# powresupply.net
KiCad netlist of a schematic drawn in EAGLE
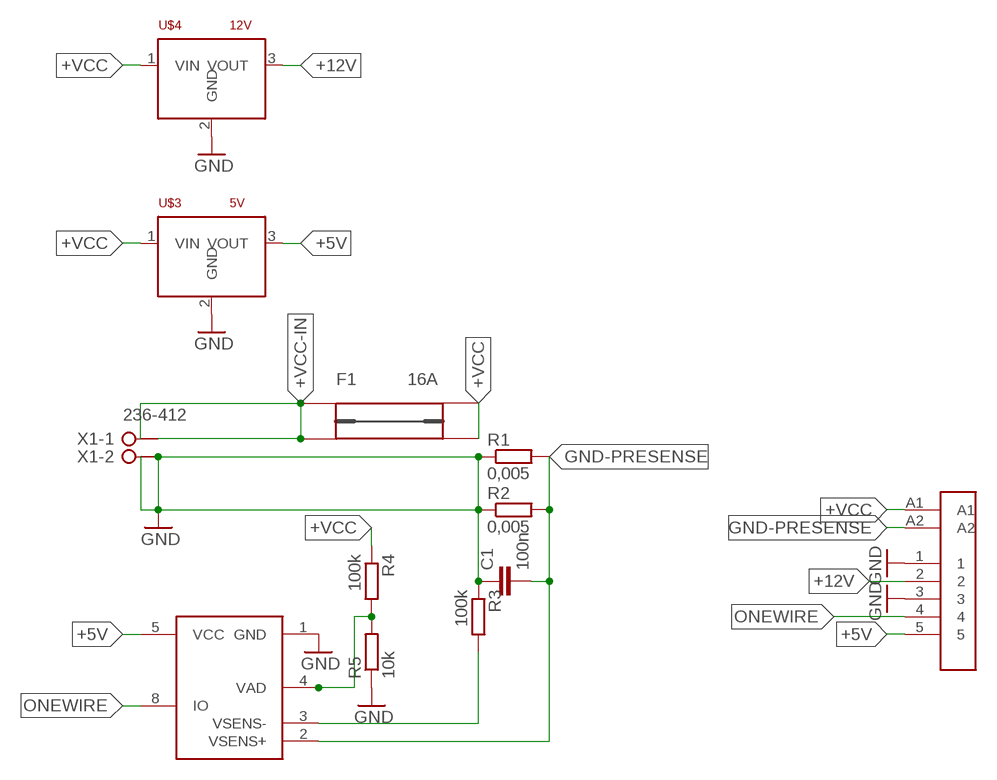
[diagram p0: schematic, sheet 1]

(export (version "E")
  (design (tool "Eeschema 10.0.6"))
  (components
    (comp (ref "C1")
      (value "100n")
      (footprint "eagle-import:C0805")
      (libsource (lib "eagle-import") (part "C-EUC0805"))
    )
    (comp (ref "F1")
      (value "16A")
      (footprint "eagle-import:1A3400")
      (libsource (lib "eagle-import") (part "BUSSMANN10X38"))
    )
    (comp (ref "R1")
      (value "0,005")
      (footprint "eagle-import:R2512")
      (libsource (lib "eagle-import") (part "R-EU_R2512"))
    )
    (comp (ref "R2")
      (value "0,005")
      (footprint "eagle-import:R2512")
      (libsource (lib "eagle-import") (part "R-EU_R2512"))
    )
    (comp (ref "R3")
      (value "100k")
      (footprint "eagle-import:R0805")
      (libsource (lib "eagle-import") (part "R-EU_R0805"))
    )
    (comp (ref "R4")
      (value "100k")
      (footprint "eagle-import:R0805")
      (libsource (lib "eagle-import") (part "R-EU_R0805"))
    )
    (comp (ref "R5")
      (value "10k")
      (footprint "eagle-import:R0805")
      (libsource (lib "eagle-import") (part "R-EU_R0805"))
    )
    (comp (ref "U$1")
      (value "7W2-F")
      (footprint "eagle-import:7W2-F")
      (libsource (lib "eagle-import") (part "7W2-F"))
    )
    (comp (ref "U$2")
      (value "DS2438")
      (footprint "eagle-import:SO-08")
      (libsource (lib "eagle-import") (part "DS2438"))
    )
    (comp (ref "U$3")
      (value "5V")
      (footprint "eagle-import:RECOM")
      (libsource (lib "eagle-import") (part "RECOM"))
    )
    (comp (ref "U$4")
      (value "12V")
      (footprint "eagle-import:RECOM")
      (libsource (lib "eagle-import") (part "RECOM"))
    )
    (comp (ref "X1")
      (value "236-412")
      (footprint "eagle-import:236-412")
      (fields (field (name "MF") "Wago Corporation") (field (name "MPN") "0236-0412"))
      (libsource (lib "eagle-import") (part "236-412"))
    )
  )
  (nets
    (net (code "1") (name "+5V") (class "Default")
      (node (ref "U$1") (pin "5") (pinfunction "5_5") (pintype "bidirectional"))
      (node (ref "U$2") (pin "5") (pinfunction "VCC_5") (pintype "bidirectional"))
      (node (ref "U$3") (pin "3") (pinfunction "VOUT_3") (pintype "power_in"))
    )
    (net (code "2") (name "+12V") (class "Default")
      (node (ref "U$1") (pin "2") (pinfunction "2_2") (pintype "bidirectional"))
      (node (ref "U$4") (pin "3") (pinfunction "VOUT_3") (pintype "power_in"))
    )
    (net (code "3") (name "+VCC") (class "Default")
      (node (ref "F1") (pin "P$3") (pinfunction "P$3_P$3") (pintype "bidirectional"))
      (node (ref "F1") (pin "P$4") (pinfunction "P$4_P$4") (pintype "bidirectional"))
      (node (ref "R4") (pin "1") (pinfunction "1_1") (pintype "passive"))
      (node (ref "U$1") (pin "A1") (pinfunction "A1_A1") (pintype "bidirectional"))
      (node (ref "U$3") (pin "1") (pinfunction "VIN_1") (pintype "power_in"))
      (node (ref "U$4") (pin "1") (pinfunction "VIN_1") (pintype "power_in"))
    )
    (net (code "4") (name "+VCC-IN") (class "Default")
      (node (ref "F1") (pin "P$1") (pinfunction "P$1_P$1") (pintype "bidirectional"))
      (node (ref "F1") (pin "P$2") (pinfunction "P$2_P$2") (pintype "bidirectional"))
      (node (ref "X1") (pin "1@1") (pinfunction "KL1_1@1") (pintype "passive"))
      (node (ref "X1") (pin "1@2") (pinfunction "KL2_1@2") (pintype "passive"))
    )
    (net (code "5") (name "GND") (class "Default")
      (node (ref "C1") (pin "1") (pinfunction "1_1") (pintype "passive"))
      (node (ref "R1") (pin "1") (pinfunction "1_1") (pintype "passive"))
      (node (ref "R2") (pin "1") (pinfunction "1_1") (pintype "passive"))
      (node (ref "R3") (pin "1") (pinfunction "1_1") (pintype "passive"))
      (node (ref "R5") (pin "1") (pinfunction "1_1") (pintype "passive"))
      (node (ref "U$1") (pin "1") (pinfunction "1_1") (pintype "bidirectional"))
      (node (ref "U$1") (pin "3") (pinfunction "3_3") (pintype "bidirectional"))
      (node (ref "U$2") (pin "1") (pinfunction "GND_1") (pintype "bidirectional"))
      (node (ref "U$3") (pin "2") (pinfunction "GND_2") (pintype "power_in"))
      (node (ref "U$4") (pin "2") (pinfunction "GND_2") (pintype "power_in"))
      (node (ref "X1") (pin "2@1") (pinfunction "KL1_2@1") (pintype "passive"))
      (node (ref "X1") (pin "2@2") (pinfunction "KL2_2@2") (pintype "passive"))
    )
    (net (code "6") (name "GND-PRESENSE") (class "Default")
      (node (ref "C1") (pin "2") (pinfunction "2_2") (pintype "passive"))
      (node (ref "R1") (pin "2") (pinfunction "2_2") (pintype "passive"))
      (node (ref "R2") (pin "2") (pinfunction "2_2") (pintype "passive"))
      (node (ref "U$1") (pin "A2") (pinfunction "A2_A2") (pintype "bidirectional"))
      (node (ref "U$2") (pin "2") (pinfunction "VSENS+_2") (pintype "bidirectional"))
    )
    (net (code "7") (name "Net-(U$2-VAD)") (class "Default")
      (node (ref "R4") (pin "2") (pinfunction "2_2") (pintype "passive"))
      (node (ref "R5") (pin "2") (pinfunction "2_2") (pintype "passive"))
      (node (ref "U$2") (pin "4") (pinfunction "VAD_4") (pintype "bidirectional"))
    )
    (net (code "8") (name "Net-(U$2-VSENS-)") (class "Default")
      (node (ref "R3") (pin "2") (pinfunction "2_2") (pintype "passive"))
      (node (ref "U$2") (pin "3") (pinfunction "VSENS-_3") (pintype "bidirectional"))
    )
    (net (code "9") (name "ONEWIRE") (class "Default")
      (node (ref "U$1") (pin "4") (pinfunction "4_4") (pintype "bidirectional"))
      (node (ref "U$2") (pin "8") (pinfunction "IO_8") (pintype "bidirectional"))
    )
  )
)
